# 2_4GPA.net
KiCad netlist of a schematic drawn in Altium Designer
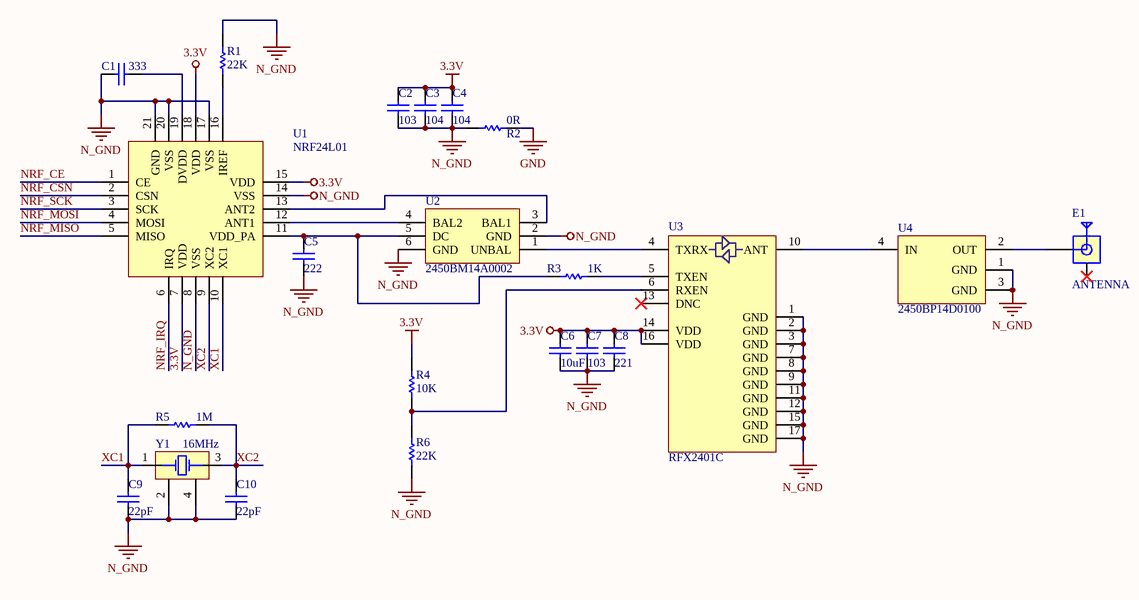
[diagram p0: 2.4GPA.SchDoc]

(export (version "E")
  (design (tool "Eeschema 10.0.6"))
  (components
    (comp (ref "C1")
      (value "333")
      (footprint "C0603")
      (description "电容")
      (fields (field (name "PUBLISHER") "Altium Limited"))
      (libsource (lib "Devices") (part "C0603"))
    )
    (comp (ref "C2")
      (value "103")
      (footprint "C0603")
      (description "电容")
      (fields (field (name "PUBLISHER") "Altium Limited"))
      (libsource (lib "Devices") (part "C0603"))
    )
    (comp (ref "C3")
      (value "104")
      (footprint "C0603")
      (description "电容")
      (fields (field (name "PUBLISHER") "Altium Limited"))
      (libsource (lib "Devices") (part "C0603"))
    )
    (comp (ref "C4")
      (value "104")
      (footprint "C0603")
      (description "电容")
      (fields (field (name "PUBLISHER") "Altium Limited"))
      (libsource (lib "Devices") (part "C0603"))
    )
    (comp (ref "C5")
      (value "222")
      (footprint "C0603")
      (description "电容")
      (fields (field (name "PUBLISHER") "Altium Limited"))
      (libsource (lib "Devices") (part "C0603"))
    )
    (comp (ref "C6")
      (value "10uF")
      (footprint "C0603")
      (description "电容")
      (fields (field (name "PUBLISHER") "Altium Limited"))
      (libsource (lib "Devices") (part "C0603"))
    )
    (comp (ref "C7")
      (value "103")
      (footprint "C0603")
      (description "电容")
      (fields (field (name "PUBLISHER") "Altium Limited"))
      (libsource (lib "Devices") (part "C0603"))
    )
    (comp (ref "C8")
      (value "221")
      (footprint "C0603")
      (description "电容")
      (fields (field (name "PUBLISHER") "Altium Limited"))
      (libsource (lib "Devices") (part "C0603"))
    )
    (comp (ref "C9")
      (value "22pF")
      (footprint "C0603")
      (description "电容")
      (fields (field (name "PUBLISHER") "Altium Limited"))
      (libsource (lib "Devices") (part "C0603"))
    )
    (comp (ref "C10")
      (value "22pF")
      (footprint "C0603")
      (description "电容")
      (fields (field (name "PUBLISHER") "Altium Limited"))
      (libsource (lib "Devices") (part "C0603"))
    )
    (comp (ref "E1") (value "ANTENNA") (footprint "SMA-KHD") (libsource (lib "Devices") (part "ANTENNA")))
    (comp (ref "R1")
      (value "22K")
      (footprint "R0603")
      (description "电阻")
      (fields (field (name "PUBLISHER") "Altium Limited"))
      (libsource (lib "Devices") (part "RES0603"))
    )
    (comp (ref "R2")
      (value "0R")
      (footprint "R0603")
      (description "电阻")
      (fields (field (name "PUBLISHER") "Altium Limited"))
      (libsource (lib "Devices") (part "RES0603"))
    )
    (comp (ref "R3")
      (value "1K")
      (footprint "R0603")
      (description "电阻")
      (fields (field (name "PUBLISHER") "Altium Limited"))
      (libsource (lib "Devices") (part "RES0603"))
    )
    (comp (ref "R4")
      (value "10K")
      (footprint "R0603")
      (description "电阻")
      (fields (field (name "PUBLISHER") "Altium Limited"))
      (libsource (lib "Devices") (part "RES0603"))
    )
    (comp (ref "R5")
      (value "1M")
      (footprint "R0603")
      (description "电阻")
      (fields (field (name "PUBLISHER") "Altium Limited"))
      (libsource (lib "Devices") (part "RES0603"))
    )
    (comp (ref "R6")
      (value "22K")
      (footprint "R0603")
      (description "电阻")
      (fields (field (name "PUBLISHER") "Altium Limited"))
      (libsource (lib "Devices") (part "RES0603"))
    )
    (comp (ref "U1") (value "NRF24L01") (footprint "QFN20") (libsource (lib "IC") (part "NRF24xx")))
    (comp (ref "U2") (value "2450BM14A0002") (footprint "0603-6") (libsource (lib "IC") (part "BALUN")))
    (comp (ref "U3") (value "RFX2401C") (footprint "QFN-16") (libsource (lib "IC") (part "RFX2401C")))
    (comp (ref "U4")
      (value "2450BP14D0100")
      (footprint "BALUN_250BP")
      (libsource (lib "IC") (part "BALUN-1"))
    )
    (comp (ref "Y1")
      (value "16MHz")
      (footprint "X-TSX-3225")
      (description "Crystal Oscillator")
      (fields (field (name "PUBLISHER") "Altium Limited"))
      (libsource (lib "Devices") (part "XTAL_1"))
    )
  )
  (nets
    (net (code "1") (name "/NRF_CE") (class "Default")
      (node (ref "U1") (pin "1") (pinfunction "CE_1") (pintype "passive"))
    )
    (net (code "2") (name "/NRF_CSN") (class "Default")
      (node (ref "U1") (pin "2") (pinfunction "CSN_2") (pintype "passive"))
    )
    (net (code "3") (name "/NRF_IRQ") (class "Default")
      (node (ref "U1") (pin "6") (pinfunction "IRQ_6") (pintype "passive"))
    )
    (net (code "4") (name "/NRF_MISO") (class "Default")
      (node (ref "U1") (pin "5") (pinfunction "MISO_5") (pintype "passive"))
    )
    (net (code "5") (name "/NRF_MOSI") (class "Default")
      (node (ref "U1") (pin "4") (pinfunction "MOSI_4") (pintype "passive"))
    )
    (net (code "6") (name "/NRF_SCK") (class "Default")
      (node (ref "U1") (pin "3") (pinfunction "SCK_3") (pintype "passive"))
    )
    (net (code "7") (name "/XC1") (class "Default")
      (node (ref "C9") (pin "2") (pinfunction "2_2") (pintype "passive"))
      (node (ref "R5") (pin "1") (pinfunction "1_1") (pintype "passive"))
      (node (ref "U1") (pin "10") (pinfunction "XC1_10") (pintype "passive"))
      (node (ref "Y1") (pin "1") (pinfunction "1_1") (pintype "passive"))
    )
    (net (code "8") (name "/XC2") (class "Default")
      (node (ref "C10") (pin "2") (pinfunction "2_2") (pintype "passive"))
      (node (ref "R5") (pin "2") (pinfunction "2_2") (pintype "passive"))
      (node (ref "U1") (pin "9") (pinfunction "XC2_9") (pintype "passive"))
      (node (ref "Y1") (pin "3") (pinfunction "3_3") (pintype "passive"))
    )
    (net (code "9") (name "3.3V") (class "Default")
      (node (ref "C2") (pin "2") (pinfunction "2_2") (pintype "passive"))
      (node (ref "C3") (pin "2") (pinfunction "2_2") (pintype "passive"))
      (node (ref "C4") (pin "2") (pinfunction "2_2") (pintype "passive"))
      (node (ref "C6") (pin "2") (pinfunction "2_2") (pintype "passive"))
      (node (ref "C7") (pin "2") (pinfunction "2_2") (pintype "passive"))
      (node (ref "C8") (pin "2") (pinfunction "2_2") (pintype "passive"))
      (node (ref "R4") (pin "1") (pinfunction "1_1") (pintype "passive"))
      (node (ref "U1") (pin "15") (pinfunction "VDD_15") (pintype "passive"))
      (node (ref "U1") (pin "18") (pinfunction "VDD_18") (pintype "passive"))
      (node (ref "U1") (pin "7") (pinfunction "VDD_7") (pintype "passive"))
      (node (ref "U3") (pin "14") (pinfunction "VDD_14") (pintype "passive"))
      (node (ref "U3") (pin "16") (pinfunction "VDD_16") (pintype "passive"))
    )
    (net (code "10") (name "GND") (class "Default")
      (node (ref "R2") (pin "1") (pinfunction "1_1") (pintype "passive"))
    )
    (net (code "11") (name "N_GND") (class "Default")
      (node (ref "C1") (pin "2") (pinfunction "2_2") (pintype "passive"))
      (node (ref "C10") (pin "1") (pinfunction "1_1") (pintype "passive"))
      (node (ref "C2") (pin "1") (pinfunction "1_1") (pintype "passive"))
      (node (ref "C3") (pin "1") (pinfunction "1_1") (pintype "passive"))
      (node (ref "C4") (pin "1") (pinfunction "1_1") (pintype "passive"))
      (node (ref "C5") (pin "1") (pinfunction "1_1") (pintype "passive"))
      (node (ref "C6") (pin "1") (pinfunction "1_1") (pintype "passive"))
      (node (ref "C7") (pin "1") (pinfunction "1_1") (pintype "passive"))
      (node (ref "C8") (pin "1") (pinfunction "1_1") (pintype "passive"))
      (node (ref "C9") (pin "1") (pinfunction "1_1") (pintype "passive"))
      (node (ref "R1") (pin "2") (pinfunction "2_2") (pintype "passive"))
      (node (ref "R2") (pin "2") (pinfunction "2_2") (pintype "passive"))
      (node (ref "R6") (pin "2") (pinfunction "2_2") (pintype "passive"))
      (node (ref "U1") (pin "14") (pinfunction "VSS_14") (pintype "passive"))
      (node (ref "U1") (pin "17") (pinfunction "VSS_17") (pintype "passive"))
      (node (ref "U1") (pin "20") (pinfunction "VSS_20") (pintype "passive"))
      (node (ref "U1") (pin "21") (pinfunction "GND_21") (pintype "passive"))
      (node (ref "U1") (pin "8") (pinfunction "VSS_8") (pintype "passive"))
      (node (ref "U2") (pin "2") (pinfunction "GND_2") (pintype "passive"))
      (node (ref "U2") (pin "6") (pinfunction "GND_6") (pintype "passive"))
      (node (ref "U3") (pin "1") (pinfunction "GND_1") (pintype "passive"))
      (node (ref "U3") (pin "11") (pinfunction "GND_11") (pintype "passive"))
      (node (ref "U3") (pin "12") (pinfunction "GND_12") (pintype "passive"))
      (node (ref "U3") (pin "15") (pinfunction "GND_15") (pintype "passive"))
      (node (ref "U3") (pin "17") (pinfunction "GND_17") (pintype "passive"))
      (node (ref "U3") (pin "2") (pinfunction "GND_2") (pintype "passive"))
      (node (ref "U3") (pin "3") (pinfunction "GND_3") (pintype "passive"))
      (node (ref "U3") (pin "7") (pinfunction "GND_7") (pintype "passive"))
      (node (ref "U3") (pin "8") (pinfunction "GND_8") (pintype "passive"))
      (node (ref "U3") (pin "9") (pinfunction "GND_9") (pintype "passive"))
      (node (ref "U4") (pin "1") (pinfunction "GND_1") (pintype "passive"))
      (node (ref "U4") (pin "3") (pinfunction "GND_3") (pintype "passive"))
      (node (ref "Y1") (pin "2") (pinfunction "2_2") (pintype "passive"))
      (node (ref "Y1") (pin "4") (pinfunction "4_4") (pintype "passive"))
    )
    (net (code "12") (name "Net-(U1-ANT1)") (class "Default")
      (node (ref "U1") (pin "12") (pinfunction "ANT1_12") (pintype "passive"))
      (node (ref "U2") (pin "4") (pinfunction "BAL2_4") (pintype "passive"))
    )
    (net (code "13") (name "Net-(U1-ANT2)") (class "Default")
      (node (ref "U1") (pin "13") (pinfunction "ANT2_13") (pintype "passive"))
      (node (ref "U2") (pin "3") (pinfunction "BAL1_3") (pintype "passive"))
    )
    (net (code "14") (name "Net-(U1-DVDD)") (class "Default")
      (node (ref "C1") (pin "1") (pinfunction "1_1") (pintype "passive"))
      (node (ref "U1") (pin "19") (pinfunction "DVDD_19") (pintype "passive"))
    )
    (net (code "15") (name "Net-(U1-IREF)") (class "Default")
      (node (ref "R1") (pin "1") (pinfunction "1_1") (pintype "passive"))
      (node (ref "U1") (pin "16") (pinfunction "IREF_16") (pintype "passive"))
    )
    (net (code "16") (name "Net-(U1-VDD_PA)") (class "Default")
      (node (ref "C5") (pin "2") (pinfunction "2_2") (pintype "passive"))
      (node (ref "R3") (pin "2") (pinfunction "2_2") (pintype "passive"))
      (node (ref "U1") (pin "11") (pinfunction "VDD_PA_11") (pintype "passive"))
      (node (ref "U2") (pin "5") (pinfunction "DC_5") (pintype "passive"))
    )
    (net (code "17") (name "Net-(U2-UNBAL)") (class "Default")
      (node (ref "U2") (pin "1") (pinfunction "UNBAL_1") (pintype "passive"))
      (node (ref "U3") (pin "4") (pinfunction "TXRX_4") (pintype "passive"))
    )
    (net (code "18") (name "Net-(U3-ANT)") (class "Default")
      (node (ref "U3") (pin "10") (pinfunction "ANT_10") (pintype "passive"))
      (node (ref "U4") (pin "4") (pinfunction "IN_4") (pintype "passive"))
    )
    (net (code "19") (name "Net-(U3-RXEN)") (class "Default")
      (node (ref "R4") (pin "2") (pinfunction "2_2") (pintype "passive"))
      (node (ref "R6") (pin "1") (pinfunction "1_1") (pintype "passive"))
      (node (ref "U3") (pin "6") (pinfunction "RXEN_6") (pintype "passive"))
    )
    (net (code "20") (name "Net-(U3-TXEN)") (class "Default")
      (node (ref "R3") (pin "1") (pinfunction "1_1") (pintype "passive"))
      (node (ref "U3") (pin "5") (pinfunction "TXEN_5") (pintype "passive"))
    )
    (net (code "21") (name "Net-(U4-OUT)") (class "Default")
      (node (ref "E1") (pin "1") (pinfunction "1_1") (pintype "passive"))
      (node (ref "U4") (pin "2") (pinfunction "OUT_2") (pintype "passive"))
    )
    (net (code "22") (name "unconnected-(E1-Pad2)") (class "Default")
      (node (ref "E1") (pin "2") (pinfunction "2_2") (pintype "power_in+no_connect"))
    )
    (net (code "23") (name "unconnected-(U3-DNC-Pad13)") (class "Default")
      (node (ref "U3") (pin "13") (pinfunction "DNC_13") (pintype "passive+no_connect"))
    )
  )
)
